# USB_To_TTL.net
KiCad netlist of a schematic drawn in Altium Designer
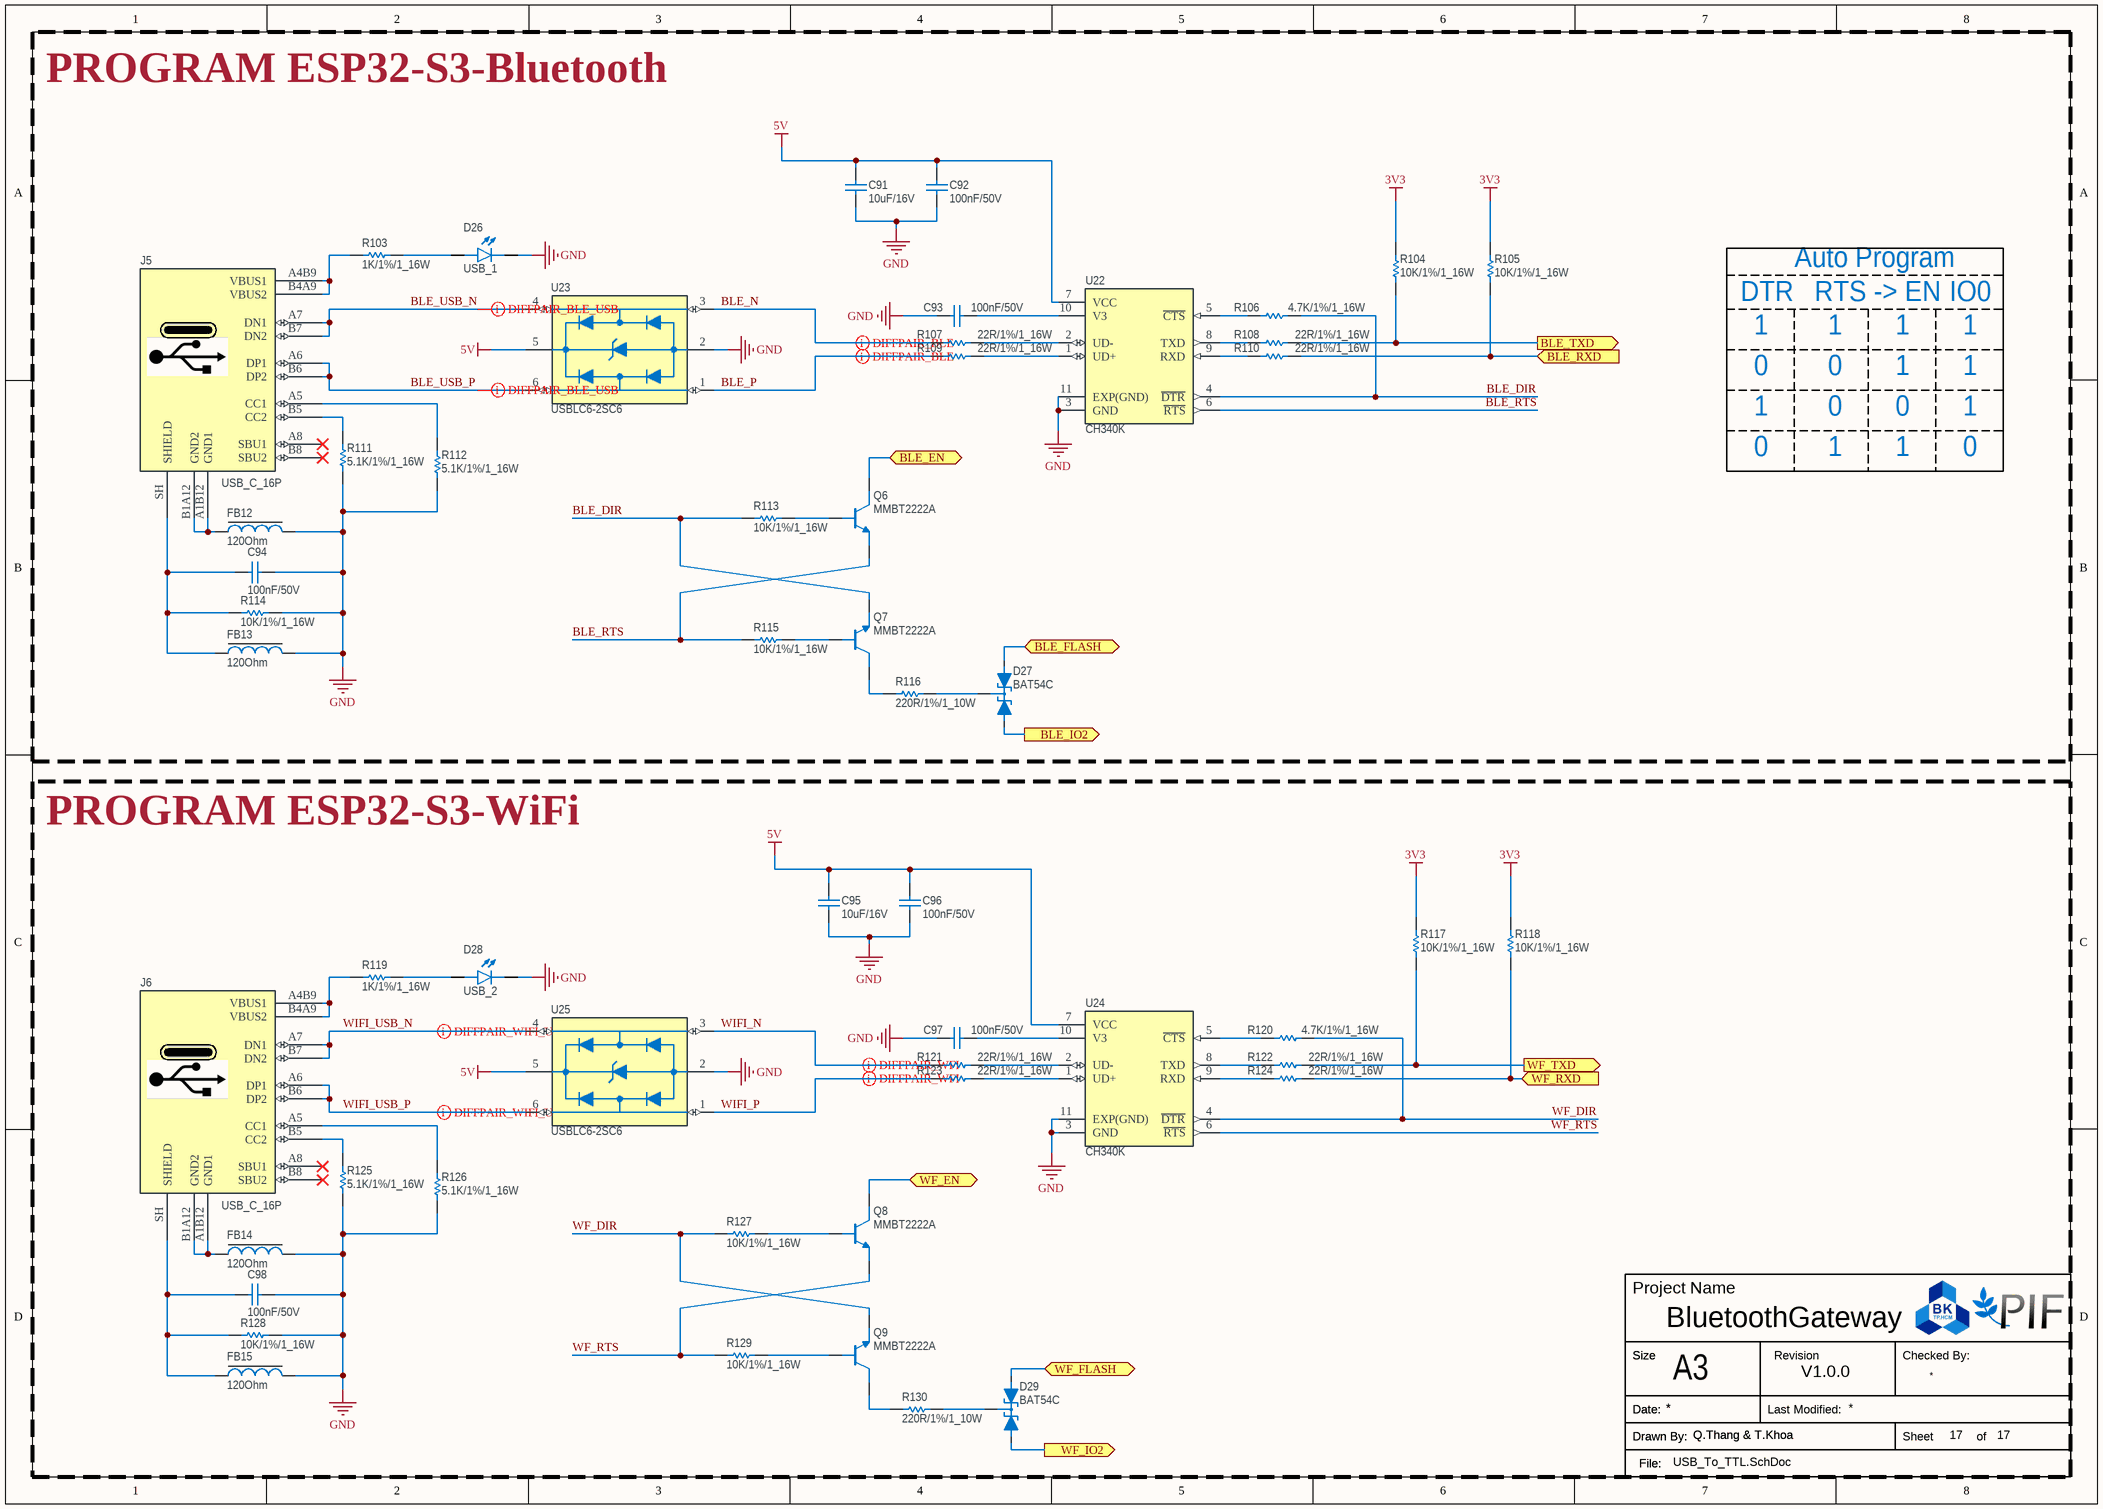
[diagram p0: USB_To_TTL.SchDoc]

(export (version "E")
  (design (tool "Eeschema 10.0.6"))
  (components
    (comp (ref "C91")
      (value "10uF/16V")
      (footprint "CAP_0603")
      (description "CAP, size 0603, 10uF, 16V")
      (fields (field (name "SUPPLY PART NUMBER") "Tụ Gốm 0603 10uF 16V"))
      (libsource (lib "BluetoothTracking") (part "Ceramic_Cap_10uF_16V_0603"))
    )
    (comp (ref "C92")
      (value "100nF/50V")
      (footprint "CAP_0603")
      (description "CAP, size 0603, 100nF, 50V")
      (fields (field (name "SUPPLY PART NUMBER") "Tụ Gốm 0603 100nF (0.1uF) 50V"))
      (libsource (lib "BluetoothTracking") (part "Ceramic_Cap_100nF_50V_0603"))
    )
    (comp (ref "C93")
      (value "100nF/50V")
      (footprint "CAP_0402")
      (description "CAP, size 0402, 100nF, 50V")
      (fields (field (name "SUPPLY PART NUMBER") "Tụ Gốm 0402 100nF (0.1uF) 50V"))
      (libsource (lib "BluetoothTracking") (part "Ceramic_Cap_100nF_50V_0402"))
    )
    (comp (ref "C94")
      (value "100nF/50V")
      (footprint "CAP_0402")
      (description "CAP, size 0402, 100nF, 50V")
      (fields (field (name "SUPPLY PART NUMBER") "Tụ Gốm 0402 100nF (0.1uF) 50V"))
      (libsource (lib "BluetoothTracking") (part "Ceramic_Cap_100nF_50V_0402"))
    )
    (comp (ref "C95")
      (value "10uF/16V")
      (footprint "CAP_0603")
      (description "CAP, size 0603, 10uF, 16V")
      (fields (field (name "SUPPLY PART NUMBER") "Tụ Gốm 0603 10uF 16V"))
      (libsource (lib "BluetoothTracking") (part "Ceramic_Cap_10uF_16V_0603"))
    )
    (comp (ref "C96")
      (value "100nF/50V")
      (footprint "CAP_0603")
      (description "CAP, size 0603, 100nF, 50V")
      (fields (field (name "SUPPLY PART NUMBER") "Tụ Gốm 0603 100nF (0.1uF) 50V"))
      (libsource (lib "BluetoothTracking") (part "Ceramic_Cap_100nF_50V_0603"))
    )
    (comp (ref "C97")
      (value "100nF/50V")
      (footprint "CAP_0402")
      (description "CAP, size 0402, 100nF, 50V")
      (fields (field (name "SUPPLY PART NUMBER") "Tụ Gốm 0402 100nF (0.1uF) 50V"))
      (libsource (lib "BluetoothTracking") (part "Ceramic_Cap_100nF_50V_0402"))
    )
    (comp (ref "C98")
      (value "100nF/50V")
      (footprint "CAP_0402")
      (description "CAP, size 0402, 100nF, 50V")
      (fields (field (name "SUPPLY PART NUMBER") "Tụ Gốm 0402 100nF (0.1uF) 50V"))
      (libsource (lib "BluetoothTracking") (part "Ceramic_Cap_100nF_50V_0402"))
    )
    (comp (ref "D26")
      (value "USB_1")
      (footprint "LED_0603Y")
      (description "LED Yellow 0603")
      (fields (field (name "SUPPLY PART NUMBER") "LED Vàng 0603 Dán SMD Trong Suốt Harvatek"))
      (libsource (lib "BluetoothTracking") (part "LED_Yellow_0603"))
    )
    (comp (ref "D27")
      (value "BAT54C")
      (footprint "SOT-23")
      (description "DIODE ARRAY SCHOTTKY 30V SOT23-3")
      (libsource (lib "BluetoothTracking") (part "BAT54C"))
    )
    (comp (ref "D28")
      (value "USB_2")
      (footprint "LED_0603Y")
      (description "LED Yellow 0603")
      (fields (field (name "SUPPLY PART NUMBER") "LED Vàng 0603 Dán SMD Trong Suốt Harvatek"))
      (libsource (lib "BluetoothTracking") (part "LED_Yellow_0603"))
    )
    (comp (ref "D29")
      (value "BAT54C")
      (footprint "SOT-23")
      (description "DIODE ARRAY SCHOTTKY 30V SOT23-3")
      (libsource (lib "BluetoothTracking") (part "BAT54C"))
    )
    (comp (ref "FB12")
      (value "120Ohm")
      (footprint "Ferrite_Bead_0805")
      (description "Ferrite Bead, size 0805, 120Ohm, 2A")
      (fields (field (name "SUPPLY PART NUMBER") "CBW201209U121T Ferrite Beads 2A 120 Ohm 0805"))
      (libsource (lib "BluetoothTracking") (part "Ferrite_Bead_120Ohm_2A_0805"))
    )
    (comp (ref "FB13")
      (value "120Ohm")
      (footprint "Ferrite_Bead_0805")
      (description "Ferrite Bead, size 0805, 120Ohm, 2A")
      (fields (field (name "SUPPLY PART NUMBER") "CBW201209U121T Ferrite Beads 2A 120 Ohm 0805"))
      (libsource (lib "BluetoothTracking") (part "Ferrite_Bead_120Ohm_2A_0805"))
    )
    (comp (ref "FB14")
      (value "120Ohm")
      (footprint "Ferrite_Bead_0805")
      (description "Ferrite Bead, size 0805, 120Ohm, 2A")
      (fields (field (name "SUPPLY PART NUMBER") "CBW201209U121T Ferrite Beads 2A 120 Ohm 0805"))
      (libsource (lib "BluetoothTracking") (part "Ferrite_Bead_120Ohm_2A_0805"))
    )
    (comp (ref "FB15")
      (value "120Ohm")
      (footprint "Ferrite_Bead_0805")
      (description "Ferrite Bead, size 0805, 120Ohm, 2A")
      (fields (field (name "SUPPLY PART NUMBER") "CBW201209U121T Ferrite Beads 2A 120 Ohm 0805"))
      (libsource (lib "BluetoothTracking") (part "Ferrite_Bead_120Ohm_2A_0805"))
    )
    (comp (ref "J5")
      (value "USB_C_16P")
      (footprint "USB_TypeC_3.1")
      (description "USB Type C - Connector, Top-mount SMT, 16pos ¦ Molex Incorporated 217179-0001")
      (fields (field (name "SUPPLY PART NUMBER") "Cổng USB Cái 3.1 Type C 16 Chân Thẳng Dán SMD"))
      (libsource (lib "BluetoothTracking") (part "USB_TypeC_3.1"))
    )
    (comp (ref "J6")
      (value "USB_C_16P")
      (footprint "USB_TypeC_3.1")
      (description "USB Type C - Connector, Top-mount SMT, 16pos ¦ Molex Incorporated 217179-0001")
      (fields (field (name "SUPPLY PART NUMBER") "Cổng USB Cái 3.1 Type C 16 Chân Thẳng Dán SMD"))
      (libsource (lib "BluetoothTracking") (part "USB_TypeC_3.1"))
    )
    (comp (ref "Q6")
      (value "MMBT2222A")
      (footprint "SOT-23")
      (description "Điện áp Vce max: 40V, dòng Ic max: 0.6A, công suất: 0.3W")
      (fields (field (name "SUPPLY PART NUMBER") "MMBT2222A 1P Transistor NPN 40V 0.6A 3 Chân SOT-23"))
      (libsource (lib "BluetoothTracking") (part "MMBT2222A"))
    )
    (comp (ref "Q7")
      (value "MMBT2222A")
      (footprint "SOT-23")
      (description "Điện áp Vce max: 40V, dòng Ic max: 0.6A, công suất: 0.3W")
      (fields (field (name "SUPPLY PART NUMBER") "MMBT2222A 1P Transistor NPN 40V 0.6A 3 Chân SOT-23"))
      (libsource (lib "BluetoothTracking") (part "MMBT2222A"))
    )
    (comp (ref "Q8")
      (value "MMBT2222A")
      (footprint "SOT-23")
      (description "Điện áp Vce max: 40V, dòng Ic max: 0.6A, công suất: 0.3W")
      (fields (field (name "SUPPLY PART NUMBER") "MMBT2222A 1P Transistor NPN 40V 0.6A 3 Chân SOT-23"))
      (libsource (lib "BluetoothTracking") (part "MMBT2222A"))
    )
    (comp (ref "Q9")
      (value "MMBT2222A")
      (footprint "SOT-23")
      (description "Điện áp Vce max: 40V, dòng Ic max: 0.6A, công suất: 0.3W")
      (fields (field (name "SUPPLY PART NUMBER") "MMBT2222A 1P Transistor NPN 40V 0.6A 3 Chân SOT-23"))
      (libsource (lib "BluetoothTracking") (part "MMBT2222A"))
    )
    (comp (ref "R103")
      (value "1K/1%/1_16W")
      (footprint "RESISTOR_0402")
      (description "Resistor 0402 1KOhm 1% 1_16W")
      (fields (field (name "SUPPLY PART NUMBER") "Điện Trở 1 KOhm 0402 1%"))
      (libsource (lib "BluetoothTracking") (part "Res_1K_0402_1%"))
    )
    (comp (ref "R104")
      (value "10K/1%/1_16W")
      (footprint "RESISTOR_0402")
      (description "Resistor 0402 10KOhm 1% 1_16W")
      (fields (field (name "SUPPLY PART NUMBER") "Điện Trở 10 KOhm 0402 1%"))
      (libsource (lib "BluetoothTracking") (part "Res_10K_0402_1%"))
    )
    (comp (ref "R105")
      (value "10K/1%/1_16W")
      (footprint "RESISTOR_0402")
      (description "Resistor 0402 10KOhm 1% 1_16W")
      (fields (field (name "SUPPLY PART NUMBER") "Điện Trở 10 KOhm 0402 1%"))
      (libsource (lib "BluetoothTracking") (part "Res_10K_0402_1%"))
    )
    (comp (ref "R106")
      (value "4.7K/1%/1_16W")
      (footprint "RESISTOR_0402")
      (description "Resistor 0402 4.7KOhm 1% 1_16W")
      (fields (field (name "SUPPLY PART NUMBER") "Điện Trở 4.7 KOhm 0402 1%"))
      (libsource (lib "BluetoothTracking") (part "Res_4.7K_0402_1%"))
    )
    (comp (ref "R107")
      (value "22R/1%/1_16W")
      (footprint "RESISTOR_0402")
      (description "Resistor 0402 22 Ohm 1% 1_16W")
      (libsource (lib "BluetoothTracking") (part "Res_22R_0402_1%"))
    )
    (comp (ref "R108")
      (value "22R/1%/1_16W")
      (footprint "RESISTOR_0402")
      (description "Resistor 0402 22 Ohm 1% 1_16W")
      (libsource (lib "BluetoothTracking") (part "Res_22R_0402_1%"))
    )
    (comp (ref "R109")
      (value "22R/1%/1_16W")
      (footprint "RESISTOR_0402")
      (description "Resistor 0402 22 Ohm 1% 1_16W")
      (libsource (lib "BluetoothTracking") (part "Res_22R_0402_1%"))
    )
    (comp (ref "R110")
      (value "22R/1%/1_16W")
      (footprint "RESISTOR_0402")
      (description "Resistor 0402 22 Ohm 1% 1_16W")
      (libsource (lib "BluetoothTracking") (part "Res_22R_0402_1%"))
    )
    (comp (ref "R111")
      (value "5.1K/1%/1_16W")
      (footprint "RESISTOR_0402")
      (description "Resistor 0402 5.1KOhm 1% 1_16W")
      (libsource (lib "BluetoothTracking") (part "Res_5.1K_0402_1%"))
    )
    (comp (ref "R112")
      (value "5.1K/1%/1_16W")
      (footprint "RESISTOR_0402")
      (description "Resistor 0402 5.1KOhm 1% 1_16W")
      (libsource (lib "BluetoothTracking") (part "Res_5.1K_0402_1%"))
    )
    (comp (ref "R113")
      (value "10K/1%/1_16W")
      (footprint "RESISTOR_0402")
      (description "Resistor 0402 10KOhm 1% 1_16W")
      (fields (field (name "SUPPLY PART NUMBER") "Điện Trở 10 KOhm 0402 1%"))
      (libsource (lib "BluetoothTracking") (part "Res_10K_0402_1%"))
    )
    (comp (ref "R114")
      (value "10K/1%/1_16W")
      (footprint "RESISTOR_0402")
      (description "Resistor 0402 10KOhm 1% 1_16W")
      (fields (field (name "SUPPLY PART NUMBER") "Điện Trở 10 KOhm 0402 1%"))
      (libsource (lib "BluetoothTracking") (part "Res_10K_0402_1%"))
    )
    (comp (ref "R115")
      (value "10K/1%/1_16W")
      (footprint "RESISTOR_0402")
      (description "Resistor 0402 10KOhm 1% 1_16W")
      (fields (field (name "SUPPLY PART NUMBER") "Điện Trở 10 KOhm 0402 1%"))
      (libsource (lib "BluetoothTracking") (part "Res_10K_0402_1%"))
    )
    (comp (ref "R116")
      (value "220R/1%/1_10W")
      (footprint "Resistor_0603")
      (description "Resistor 0603 220 Ohm 1% 1_10W")
      (fields (field (name "SUPPLY PART NUMBER") "Điện Trở 220 Ohm 0603 1%"))
      (libsource (lib "BluetoothTracking") (part "Res_220R_0603_1%"))
    )
    (comp (ref "R117")
      (value "10K/1%/1_16W")
      (footprint "RESISTOR_0402")
      (description "Resistor 0402 10KOhm 1% 1_16W")
      (fields (field (name "SUPPLY PART NUMBER") "Điện Trở 10 KOhm 0402 1%"))
      (libsource (lib "BluetoothTracking") (part "Res_10K_0402_1%"))
    )
    (comp (ref "R118")
      (value "10K/1%/1_16W")
      (footprint "RESISTOR_0402")
      (description "Resistor 0402 10KOhm 1% 1_16W")
      (fields (field (name "SUPPLY PART NUMBER") "Điện Trở 10 KOhm 0402 1%"))
      (libsource (lib "BluetoothTracking") (part "Res_10K_0402_1%"))
    )
    (comp (ref "R119")
      (value "1K/1%/1_16W")
      (footprint "RESISTOR_0402")
      (description "Resistor 0402 1KOhm 1% 1_16W")
      (fields (field (name "SUPPLY PART NUMBER") "Điện Trở 1 KOhm 0402 1%"))
      (libsource (lib "BluetoothTracking") (part "Res_1K_0402_1%"))
    )
    (comp (ref "R120")
      (value "4.7K/1%/1_16W")
      (footprint "RESISTOR_0402")
      (description "Resistor 0402 4.7KOhm 1% 1_16W")
      (fields (field (name "SUPPLY PART NUMBER") "Điện Trở 4.7 KOhm 0402 1%"))
      (libsource (lib "BluetoothTracking") (part "Res_4.7K_0402_1%"))
    )
    (comp (ref "R121")
      (value "22R/1%/1_16W")
      (footprint "RESISTOR_0402")
      (description "Resistor 0402 22 Ohm 1% 1_16W")
      (libsource (lib "BluetoothTracking") (part "Res_22R_0402_1%"))
    )
    (comp (ref "R122")
      (value "22R/1%/1_16W")
      (footprint "RESISTOR_0402")
      (description "Resistor 0402 22 Ohm 1% 1_16W")
      (libsource (lib "BluetoothTracking") (part "Res_22R_0402_1%"))
    )
    (comp (ref "R123")
      (value "22R/1%/1_16W")
      (footprint "RESISTOR_0402")
      (description "Resistor 0402 22 Ohm 1% 1_16W")
      (libsource (lib "BluetoothTracking") (part "Res_22R_0402_1%"))
    )
    (comp (ref "R124")
      (value "22R/1%/1_16W")
      (footprint "RESISTOR_0402")
      (description "Resistor 0402 22 Ohm 1% 1_16W")
      (libsource (lib "BluetoothTracking") (part "Res_22R_0402_1%"))
    )
    (comp (ref "R125")
      (value "5.1K/1%/1_16W")
      (footprint "RESISTOR_0402")
      (description "Resistor 0402 5.1KOhm 1% 1_16W")
      (libsource (lib "BluetoothTracking") (part "Res_5.1K_0402_1%"))
    )
    (comp (ref "R126")
      (value "5.1K/1%/1_16W")
      (footprint "RESISTOR_0402")
      (description "Resistor 0402 5.1KOhm 1% 1_16W")
      (libsource (lib "BluetoothTracking") (part "Res_5.1K_0402_1%"))
    )
    (comp (ref "R127")
      (value "10K/1%/1_16W")
      (footprint "RESISTOR_0402")
      (description "Resistor 0402 10KOhm 1% 1_16W")
      (fields (field (name "SUPPLY PART NUMBER") "Điện Trở 10 KOhm 0402 1%"))
      (libsource (lib "BluetoothTracking") (part "Res_10K_0402_1%"))
    )
    (comp (ref "R128")
      (value "10K/1%/1_16W")
      (footprint "RESISTOR_0402")
      (description "Resistor 0402 10KOhm 1% 1_16W")
      (fields (field (name "SUPPLY PART NUMBER") "Điện Trở 10 KOhm 0402 1%"))
      (libsource (lib "BluetoothTracking") (part "Res_10K_0402_1%"))
    )
    (comp (ref "R129")
      (value "10K/1%/1_16W")
      (footprint "RESISTOR_0402")
      (description "Resistor 0402 10KOhm 1% 1_16W")
      (fields (field (name "SUPPLY PART NUMBER") "Điện Trở 10 KOhm 0402 1%"))
      (libsource (lib "BluetoothTracking") (part "Res_10K_0402_1%"))
    )
    (comp (ref "R130")
      (value "220R/1%/1_10W")
      (footprint "Resistor_0603")
      (description "Resistor 0603 220 Ohm 1% 1_10W")
      (fields (field (name "SUPPLY PART NUMBER") "Điện Trở 220 Ohm 0603 1%"))
      (libsource (lib "BluetoothTracking") (part "Res_220R_0603_1%"))
    )
    (comp (ref "U22")
      (value "CH340K")
      (footprint "EESOP10")
      (description "USB to Serial Port Chip")
      (libsource (lib "BluetoothTracking") (part "CH340K"))
    )
    (comp (ref "U23")
      (value "USBLC6-2SC6")
      (footprint "SOT-23-6")
      (description "17V Clamp 5A (8/20Âµs) Ipp Tvs Diode Surface Mount SOT-23-6")
      (fields (field (name "SUPPLY PART NUMBER") "USBLC6-2SC6 TVS diode 5.25V 17V SOT23-6"))
      (libsource (lib "BluetoothTracking") (part "USBLC6-2SC6"))
    )
    (comp (ref "U24")
      (value "CH340K")
      (footprint "EESOP10")
      (description "USB to Serial Port Chip")
      (libsource (lib "BluetoothTracking") (part "CH340K"))
    )
    (comp (ref "U25")
      (value "USBLC6-2SC6")
      (footprint "SOT-23-6")
      (description "17V Clamp 5A (8/20Âµs) Ipp Tvs Diode Surface Mount SOT-23-6")
      (fields (field (name "SUPPLY PART NUMBER") "USBLC6-2SC6 TVS diode 5.25V 17V SOT23-6"))
      (libsource (lib "BluetoothTracking") (part "USBLC6-2SC6"))
    )
  )
  (nets
    (net (code "1") (name "/BLE_DIR") (class "Default")
      (node (ref "Q7") (pin "2") (pinfunction "E_2") (pintype "passive"))
      (node (ref "R106") (pin "2") (pinfunction "2_2") (pintype "passive"))
      (node (ref "R113") (pin "1") (pinfunction "1_1") (pintype "passive"))
      (node (ref "U22") (pin "4") (pinfunction "~{DTR}_4") (pintype "output"))
    )
    (net (code "2") (name "/BLE_EN") (class "Default")
      (node (ref "Q6") (pin "3") (pinfunction "C_3") (pintype "passive"))
    )
    (net (code "3") (name "/BLE_FLASH") (class "Default")
      (node (ref "D27") (pin "2") (pinfunction "A2_2") (pintype "passive"))
    )
    (net (code "4") (name "/BLE_IO2") (class "Default")
      (node (ref "D27") (pin "1") (pinfunction "A1_1") (pintype "passive"))
    )
    (net (code "5") (name "/BLE_N") (class "Default")
      (node (ref "R107") (pin "1") (pinfunction "1_1") (pintype "passive"))
      (node (ref "U23") (pin "3") (pinfunction "I/O2_IN_3") (pintype "bidirectional"))
    )
    (net (code "6") (name "/BLE_P") (class "Default")
      (node (ref "R109") (pin "1") (pinfunction "1_1") (pintype "passive"))
      (node (ref "U23") (pin "1") (pinfunction "I/O1_IN_1") (pintype "bidirectional"))
    )
    (net (code "7") (name "/BLE_RTS") (class "Default")
      (node (ref "Q6") (pin "2") (pinfunction "E_2") (pintype "passive"))
      (node (ref "R115") (pin "1") (pinfunction "1_1") (pintype "passive"))
      (node (ref "U22") (pin "6") (pinfunction "~{RTS}_6") (pintype "output"))
    )
    (net (code "8") (name "/BLE_RXD") (class "Default")
      (node (ref "R105") (pin "1") (pinfunction "1_1") (pintype "passive"))
      (node (ref "R110") (pin "2") (pinfunction "2_2") (pintype "passive"))
    )
    (net (code "9") (name "/BLE_TXD") (class "Default")
      (node (ref "R104") (pin "1") (pinfunction "1_1") (pintype "passive"))
      (node (ref "R108") (pin "2") (pinfunction "2_2") (pintype "passive"))
    )
    (net (code "10") (name "/BLE_USB_N") (class "Default")
      (node (ref "J5") (pin "A7") (pinfunction "DN1_A7") (pintype "bidirectional"))
      (node (ref "J5") (pin "B7") (pinfunction "DN2_B7") (pintype "bidirectional"))
      (node (ref "U23") (pin "4") (pinfunction "I/O2_OUT_4") (pintype "bidirectional"))
    )
    (net (code "11") (name "/BLE_USB_P") (class "Default")
      (node (ref "J5") (pin "A6") (pinfunction "DP1_A6") (pintype "bidirectional"))
      (node (ref "J5") (pin "B6") (pinfunction "DP2_B6") (pintype "bidirectional"))
      (node (ref "U23") (pin "6") (pinfunction "I/O1_OUT_6") (pintype "bidirectional"))
    )
    (net (code "12") (name "/WF_DIR") (class "Default")
      (node (ref "Q9") (pin "2") (pinfunction "E_2") (pintype "passive"))
      (node (ref "R120") (pin "2") (pinfunction "2_2") (pintype "passive"))
      (node (ref "R127") (pin "1") (pinfunction "1_1") (pintype "passive"))
      (node (ref "U24") (pin "4") (pinfunction "~{DTR}_4") (pintype "output"))
    )
    (net (code "13") (name "/WF_EN") (class "Default")
      (node (ref "Q8") (pin "3") (pinfunction "C_3") (pintype "passive"))
    )
    (net (code "14") (name "/WF_FLASH") (class "Default")
      (node (ref "D29") (pin "2") (pinfunction "A2_2") (pintype "passive"))
    )
    (net (code "15") (name "/WF_IO2") (class "Default")
      (node (ref "D29") (pin "1") (pinfunction "A1_1") (pintype "passive"))
    )
    (net (code "16") (name "/WF_RTS") (class "Default")
      (node (ref "Q8") (pin "2") (pinfunction "E_2") (pintype "passive"))
      (node (ref "R129") (pin "1") (pinfunction "1_1") (pintype "passive"))
      (node (ref "U24") (pin "6") (pinfunction "~{RTS}_6") (pintype "output"))
    )
    (net (code "17") (name "/WF_RXD") (class "Default")
      (node (ref "R118") (pin "1") (pinfunction "1_1") (pintype "passive"))
      (node (ref "R124") (pin "2") (pinfunction "2_2") (pintype "passive"))
    )
    (net (code "18") (name "/WF_TXD") (class "Default")
      (node (ref "R117") (pin "1") (pinfunction "1_1") (pintype "passive"))
      (node (ref "R122") (pin "2") (pinfunction "2_2") (pintype "passive"))
    )
    (net (code "19") (name "/WIFI_N") (class "Default")
      (node (ref "R121") (pin "1") (pinfunction "1_1") (pintype "passive"))
      (node (ref "U25") (pin "3") (pinfunction "I/O2_IN_3") (pintype "bidirectional"))
    )
    (net (code "20") (name "/WIFI_P") (class "Default")
      (node (ref "R123") (pin "1") (pinfunction "1_1") (pintype "passive"))
      (node (ref "U25") (pin "1") (pinfunction "I/O1_IN_1") (pintype "bidirectional"))
    )
    (net (code "21") (name "/WIFI_USB_N") (class "Default")
      (node (ref "J6") (pin "A7") (pinfunction "DN1_A7") (pintype "bidirectional"))
      (node (ref "J6") (pin "B7") (pinfunction "DN2_B7") (pintype "bidirectional"))
      (node (ref "U25") (pin "4") (pinfunction "I/O2_OUT_4") (pintype "bidirectional"))
    )
    (net (code "22") (name "/WIFI_USB_P") (class "Default")
      (node (ref "J6") (pin "A6") (pinfunction "DP1_A6") (pintype "bidirectional"))
      (node (ref "J6") (pin "B6") (pinfunction "DP2_B6") (pintype "bidirectional"))
      (node (ref "U25") (pin "6") (pinfunction "I/O1_OUT_6") (pintype "bidirectional"))
    )
    (net (code "23") (name "3V3") (class "Default")
      (node (ref "R104") (pin "2") (pinfunction "2_2") (pintype "passive"))
      (node (ref "R105") (pin "2") (pinfunction "2_2") (pintype "passive"))
      (node (ref "R117") (pin "2") (pinfunction "2_2") (pintype "passive"))
      (node (ref "R118") (pin "2") (pinfunction "2_2") (pintype "passive"))
    )
    (net (code "24") (name "5V") (class "Default")
      (node (ref "C91") (pin "2") (pinfunction "2_2") (pintype "passive"))
      (node (ref "C92") (pin "2") (pinfunction "2_2") (pintype "passive"))
      (node (ref "C95") (pin "2") (pinfunction "2_2") (pintype "passive"))
      (node (ref "C96") (pin "2") (pinfunction "2_2") (pintype "passive"))
      (node (ref "U22") (pin "7") (pinfunction "VCC_7") (pintype "power_in"))
      (node (ref "U23") (pin "5") (pinfunction "VBUS_5") (pintype "power_in"))
      (node (ref "U24") (pin "7") (pinfunction "VCC_7") (pintype "power_in"))
      (node (ref "U25") (pin "5") (pinfunction "VBUS_5") (pintype "power_in"))
    )
    (net (code "25") (name "GND") (class "Default")
      (node (ref "C91") (pin "1") (pinfunction "1_1") (pintype "passive"))
      (node (ref "C92") (pin "1") (pinfunction "1_1") (pintype "passive"))
      (node (ref "C93") (pin "1") (pinfunction "1_1") (pintype "passive"))
      (node (ref "C94") (pin "2") (pinfunction "2_2") (pintype "passive"))
      (node (ref "C95") (pin "1") (pinfunction "1_1") (pintype "passive"))
      (node (ref "C96") (pin "1") (pinfunction "1_1") (pintype "passive"))
      (node (ref "C97") (pin "1") (pinfunction "1_1") (pintype "passive"))
      (node (ref "C98") (pin "2") (pinfunction "2_2") (pintype "passive"))
      (node (ref "D26") (pin "C") (pinfunction "C_C") (pintype "passive"))
      (node (ref "D28") (pin "C") (pinfunction "C_C") (pintype "passive"))
      (node (ref "FB12") (pin "2") (pinfunction "2_2") (pintype "passive"))
      (node (ref "FB13") (pin "2") (pinfunction "2_2") (pintype "passive"))
      (node (ref "FB14") (pin "2") (pinfunction "2_2") (pintype "passive"))
      (node (ref "FB15") (pin "2") (pinfunction "2_2") (pintype "passive"))
      (node (ref "R111") (pin "1") (pinfunction "1_1") (pintype "passive"))
      (node (ref "R112") (pin "1") (pinfunction "1_1") (pintype "passive"))
      (node (ref "R114") (pin "2") (pinfunction "2_2") (pintype "passive"))
      (node (ref "R125") (pin "1") (pinfunction "1_1") (pintype "passive"))
      (node (ref "R126") (pin "1") (pinfunction "1_1") (pintype "passive"))
      (node (ref "R128") (pin "2") (pinfunction "2_2") (pintype "passive"))
      (node (ref "U22") (pin "11") (pinfunction "EXP(GND)_11") (pintype "power_in"))
      (node (ref "U22") (pin "3") (pinfunction "GND_3") (pintype "power_in"))
      (node (ref "U23") (pin "2") (pinfunction "GND_2") (pintype "power_in"))
      (node (ref "U24") (pin "11") (pinfunction "EXP(GND)_11") (pintype "power_in"))
      (node (ref "U24") (pin "3") (pinfunction "GND_3") (pintype "power_in"))
      (node (ref "U25") (pin "2") (pinfunction "GND_2") (pintype "power_in"))
    )
    (net (code "26") (name "Net-(D26-PadA)") (class "Default")
      (node (ref "D26") (pin "A") (pinfunction "A_A") (pintype "passive"))
      (node (ref "R103") (pin "2") (pinfunction "2_2") (pintype "passive"))
    )
    (net (code "27") (name "Net-(D27-C)") (class "Default")
      (node (ref "D27") (pin "3") (pinfunction "C_3") (pintype "passive"))
      (node (ref "R116") (pin "2") (pinfunction "2_2") (pintype "passive"))
    )
    (net (code "28") (name "Net-(D28-PadA)") (class "Default")
      (node (ref "D28") (pin "A") (pinfunction "A_A") (pintype "passive"))
      (node (ref "R119") (pin "2") (pinfunction "2_2") (pintype "passive"))
    )
    (net (code "29") (name "Net-(D29-C)") (class "Default")
      (node (ref "D29") (pin "3") (pinfunction "C_3") (pintype "passive"))
      (node (ref "R130") (pin "2") (pinfunction "2_2") (pintype "passive"))
    )
    (net (code "30") (name "Net-(J5-CC1)") (class "Default")
      (node (ref "J5") (pin "A5") (pinfunction "CC1_A5") (pintype "bidirectional"))
      (node (ref "R112") (pin "2") (pinfunction "2_2") (pintype "passive"))
    )
    (net (code "31") (name "Net-(J5-CC2)") (class "Default")
      (node (ref "J5") (pin "B5") (pinfunction "CC2_B5") (pintype "bidirectional"))
      (node (ref "R111") (pin "2") (pinfunction "2_2") (pintype "passive"))
    )
    (net (code "32") (name "Net-(J5-GND1)") (class "Default")
      (node (ref "FB12") (pin "1") (pinfunction "1_1") (pintype "passive"))
      (node (ref "J5") (pin "A1B12") (pinfunction "GND1_A1B12") (pintype "power_in"))
      (node (ref "J5") (pin "B1A12") (pinfunction "GND2_B1A12") (pintype "power_in"))
    )
    (net (code "33") (name "Net-(J5-SHIELD)") (class "Default")
      (node (ref "C94") (pin "1") (pinfunction "1_1") (pintype "passive"))
      (node (ref "FB13") (pin "1") (pinfunction "1_1") (pintype "passive"))
      (node (ref "J5") (pin "SH") (pinfunction "SHIELD_SH") (pintype "passive"))
      (node (ref "R114") (pin "1") (pinfunction "1_1") (pintype "passive"))
    )
    (net (code "34") (name "Net-(J5-VBUS1)") (class "Default")
      (node (ref "J5") (pin "A4B9") (pinfunction "VBUS1_A4B9") (pintype "power_in"))
      (node (ref "J5") (pin "B4A9") (pinfunction "VBUS2_B4A9") (pintype "power_in"))
      (node (ref "R103") (pin "1") (pinfunction "1_1") (pintype "passive"))
    )
    (net (code "35") (name "Net-(J6-CC1)") (class "Default")
      (node (ref "J6") (pin "A5") (pinfunction "CC1_A5") (pintype "bidirectional"))
      (node (ref "R126") (pin "2") (pinfunction "2_2") (pintype "passive"))
    )
    (net (code "36") (name "Net-(J6-CC2)") (class "Default")
      (node (ref "J6") (pin "B5") (pinfunction "CC2_B5") (pintype "bidirectional"))
      (node (ref "R125") (pin "2") (pinfunction "2_2") (pintype "passive"))
    )
    (net (code "37") (name "Net-(J6-GND1)") (class "Default")
      (node (ref "FB14") (pin "1") (pinfunction "1_1") (pintype "passive"))
      (node (ref "J6") (pin "A1B12") (pinfunction "GND1_A1B12") (pintype "power_in"))
      (node (ref "J6") (pin "B1A12") (pinfunction "GND2_B1A12") (pintype "power_in"))
    )
    (net (code "38") (name "Net-(J6-SHIELD)") (class "Default")
      (node (ref "C98") (pin "1") (pinfunction "1_1") (pintype "passive"))
      (node (ref "FB15") (pin "1") (pinfunction "1_1") (pintype "passive"))
      (node (ref "J6") (pin "SH") (pinfunction "SHIELD_SH") (pintype "passive"))
      (node (ref "R128") (pin "1") (pinfunction "1_1") (pintype "passive"))
    )
    (net (code "39") (name "Net-(J6-VBUS1)") (class "Default")
      (node (ref "J6") (pin "A4B9") (pinfunction "VBUS1_A4B9") (pintype "power_in"))
      (node (ref "J6") (pin "B4A9") (pinfunction "VBUS2_B4A9") (pintype "power_in"))
      (node (ref "R119") (pin "1") (pinfunction "1_1") (pintype "passive"))
    )
    (net (code "40") (name "Net-(Q6-B)") (class "Default")
      (node (ref "Q6") (pin "1") (pinfunction "B_1") (pintype "passive"))
      (node (ref "R113") (pin "2") (pinfunction "2_2") (pintype "passive"))
    )
    (net (code "41") (name "Net-(Q7-B)") (class "Default")
      (node (ref "Q7") (pin "1") (pinfunction "B_1") (pintype "passive"))
      (node (ref "R115") (pin "2") (pinfunction "2_2") (pintype "passive"))
    )
    (net (code "42") (name "Net-(Q7-C)") (class "Default")
      (node (ref "Q7") (pin "3") (pinfunction "C_3") (pintype "passive"))
      (node (ref "R116") (pin "1") (pinfunction "1_1") (pintype "passive"))
    )
    (net (code "43") (name "Net-(Q8-B)") (class "Default")
      (node (ref "Q8") (pin "1") (pinfunction "B_1") (pintype "passive"))
      (node (ref "R127") (pin "2") (pinfunction "2_2") (pintype "passive"))
    )
    (net (code "44") (name "Net-(Q9-B)") (class "Default")
      (node (ref "Q9") (pin "1") (pinfunction "B_1") (pintype "passive"))
      (node (ref "R129") (pin "2") (pinfunction "2_2") (pintype "passive"))
    )
    (net (code "45") (name "Net-(Q9-C)") (class "Default")
      (node (ref "Q9") (pin "3") (pinfunction "C_3") (pintype "passive"))
      (node (ref "R130") (pin "1") (pinfunction "1_1") (pintype "passive"))
    )
    (net (code "46") (name "Net-(U22-RXD)") (class "Default")
      (node (ref "R110") (pin "1") (pinfunction "1_1") (pintype "passive"))
      (node (ref "U22") (pin "9") (pinfunction "RXD_9") (pintype "input"))
    )
    (net (code "47") (name "Net-(U22-TXD)") (class "Default")
      (node (ref "R108") (pin "1") (pinfunction "1_1") (pintype "passive"))
      (node (ref "U22") (pin "8") (pinfunction "TXD_8") (pintype "output"))
    )
    (net (code "48") (name "Net-(U22-UD+)") (class "Default")
      (node (ref "R109") (pin "2") (pinfunction "2_2") (pintype "passive"))
      (node (ref "U22") (pin "1") (pinfunction "UD+_1") (pintype "bidirectional"))
    )
    (net (code "49") (name "Net-(U22-UD-)") (class "Default")
      (node (ref "R107") (pin "2") (pinfunction "2_2") (pintype "passive"))
      (node (ref "U22") (pin "2") (pinfunction "UD-_2") (pintype "bidirectional"))
    )
    (net (code "50") (name "Net-(U22-V3)") (class "Default")
      (node (ref "C93") (pin "2") (pinfunction "2_2") (pintype "passive"))
      (node (ref "U22") (pin "10") (pinfunction "V3_10") (pintype "power_in"))
    )
    (net (code "51") (name "Net-(U22-~{CTS})") (class "Default")
      (node (ref "R106") (pin "1") (pinfunction "1_1") (pintype "passive"))
      (node (ref "U22") (pin "5") (pinfunction "~{CTS}_5") (pintype "input"))
    )
    (net (code "52") (name "Net-(U24-RXD)") (class "Default")
      (node (ref "R124") (pin "1") (pinfunction "1_1") (pintype "passive"))
      (node (ref "U24") (pin "9") (pinfunction "RXD_9") (pintype "input"))
    )
    (net (code "53") (name "Net-(U24-TXD)") (class "Default")
      (node (ref "R122") (pin "1") (pinfunction "1_1") (pintype "passive"))
      (node (ref "U24") (pin "8") (pinfunction "TXD_8") (pintype "output"))
    )
    (net (code "54") (name "Net-(U24-UD+)") (class "Default")
      (node (ref "R123") (pin "2") (pinfunction "2_2") (pintype "passive"))
      (node (ref "U24") (pin "1") (pinfunction "UD+_1") (pintype "bidirectional"))
    )
    (net (code "55") (name "Net-(U24-UD-)") (class "Default")
      (node (ref "R121") (pin "2") (pinfunction "2_2") (pintype "passive"))
      (node (ref "U24") (pin "2") (pinfunction "UD-_2") (pintype "bidirectional"))
    )
    (net (code "56") (name "Net-(U24-V3)") (class "Default")
      (node (ref "C97") (pin "2") (pinfunction "2_2") (pintype "passive"))
      (node (ref "U24") (pin "10") (pinfunction "V3_10") (pintype "power_in"))
    )
    (net (code "57") (name "Net-(U24-~{CTS})") (class "Default")
      (node (ref "R120") (pin "1") (pinfunction "1_1") (pintype "passive"))
      (node (ref "U24") (pin "5") (pinfunction "~{CTS}_5") (pintype "input"))
    )
    (net (code "58") (name "unconnected-(J5-SBU1-PadA8)") (class "Default")
      (node (ref "J5") (pin "A8") (pinfunction "SBU1_A8") (pintype "bidirectional+no_connect"))
    )
    (net (code "59") (name "unconnected-(J5-SBU2-PadB8)") (class "Default")
      (node (ref "J5") (pin "B8") (pinfunction "SBU2_B8") (pintype "bidirectional+no_connect"))
    )
    (net (code "60") (name "unconnected-(J6-SBU1-PadA8)") (class "Default")
      (node (ref "J6") (pin "A8") (pinfunction "SBU1_A8") (pintype "bidirectional+no_connect"))
    )
    (net (code "61") (name "unconnected-(J6-SBU2-PadB8)") (class "Default")
      (node (ref "J6") (pin "B8") (pinfunction "SBU2_B8") (pintype "bidirectional+no_connect"))
    )
  )
)
